# ProPrj_UNO_SIG_pro_2026-06-11.net
KiCad netlist of a schematic drawn in EasyEDA Pro
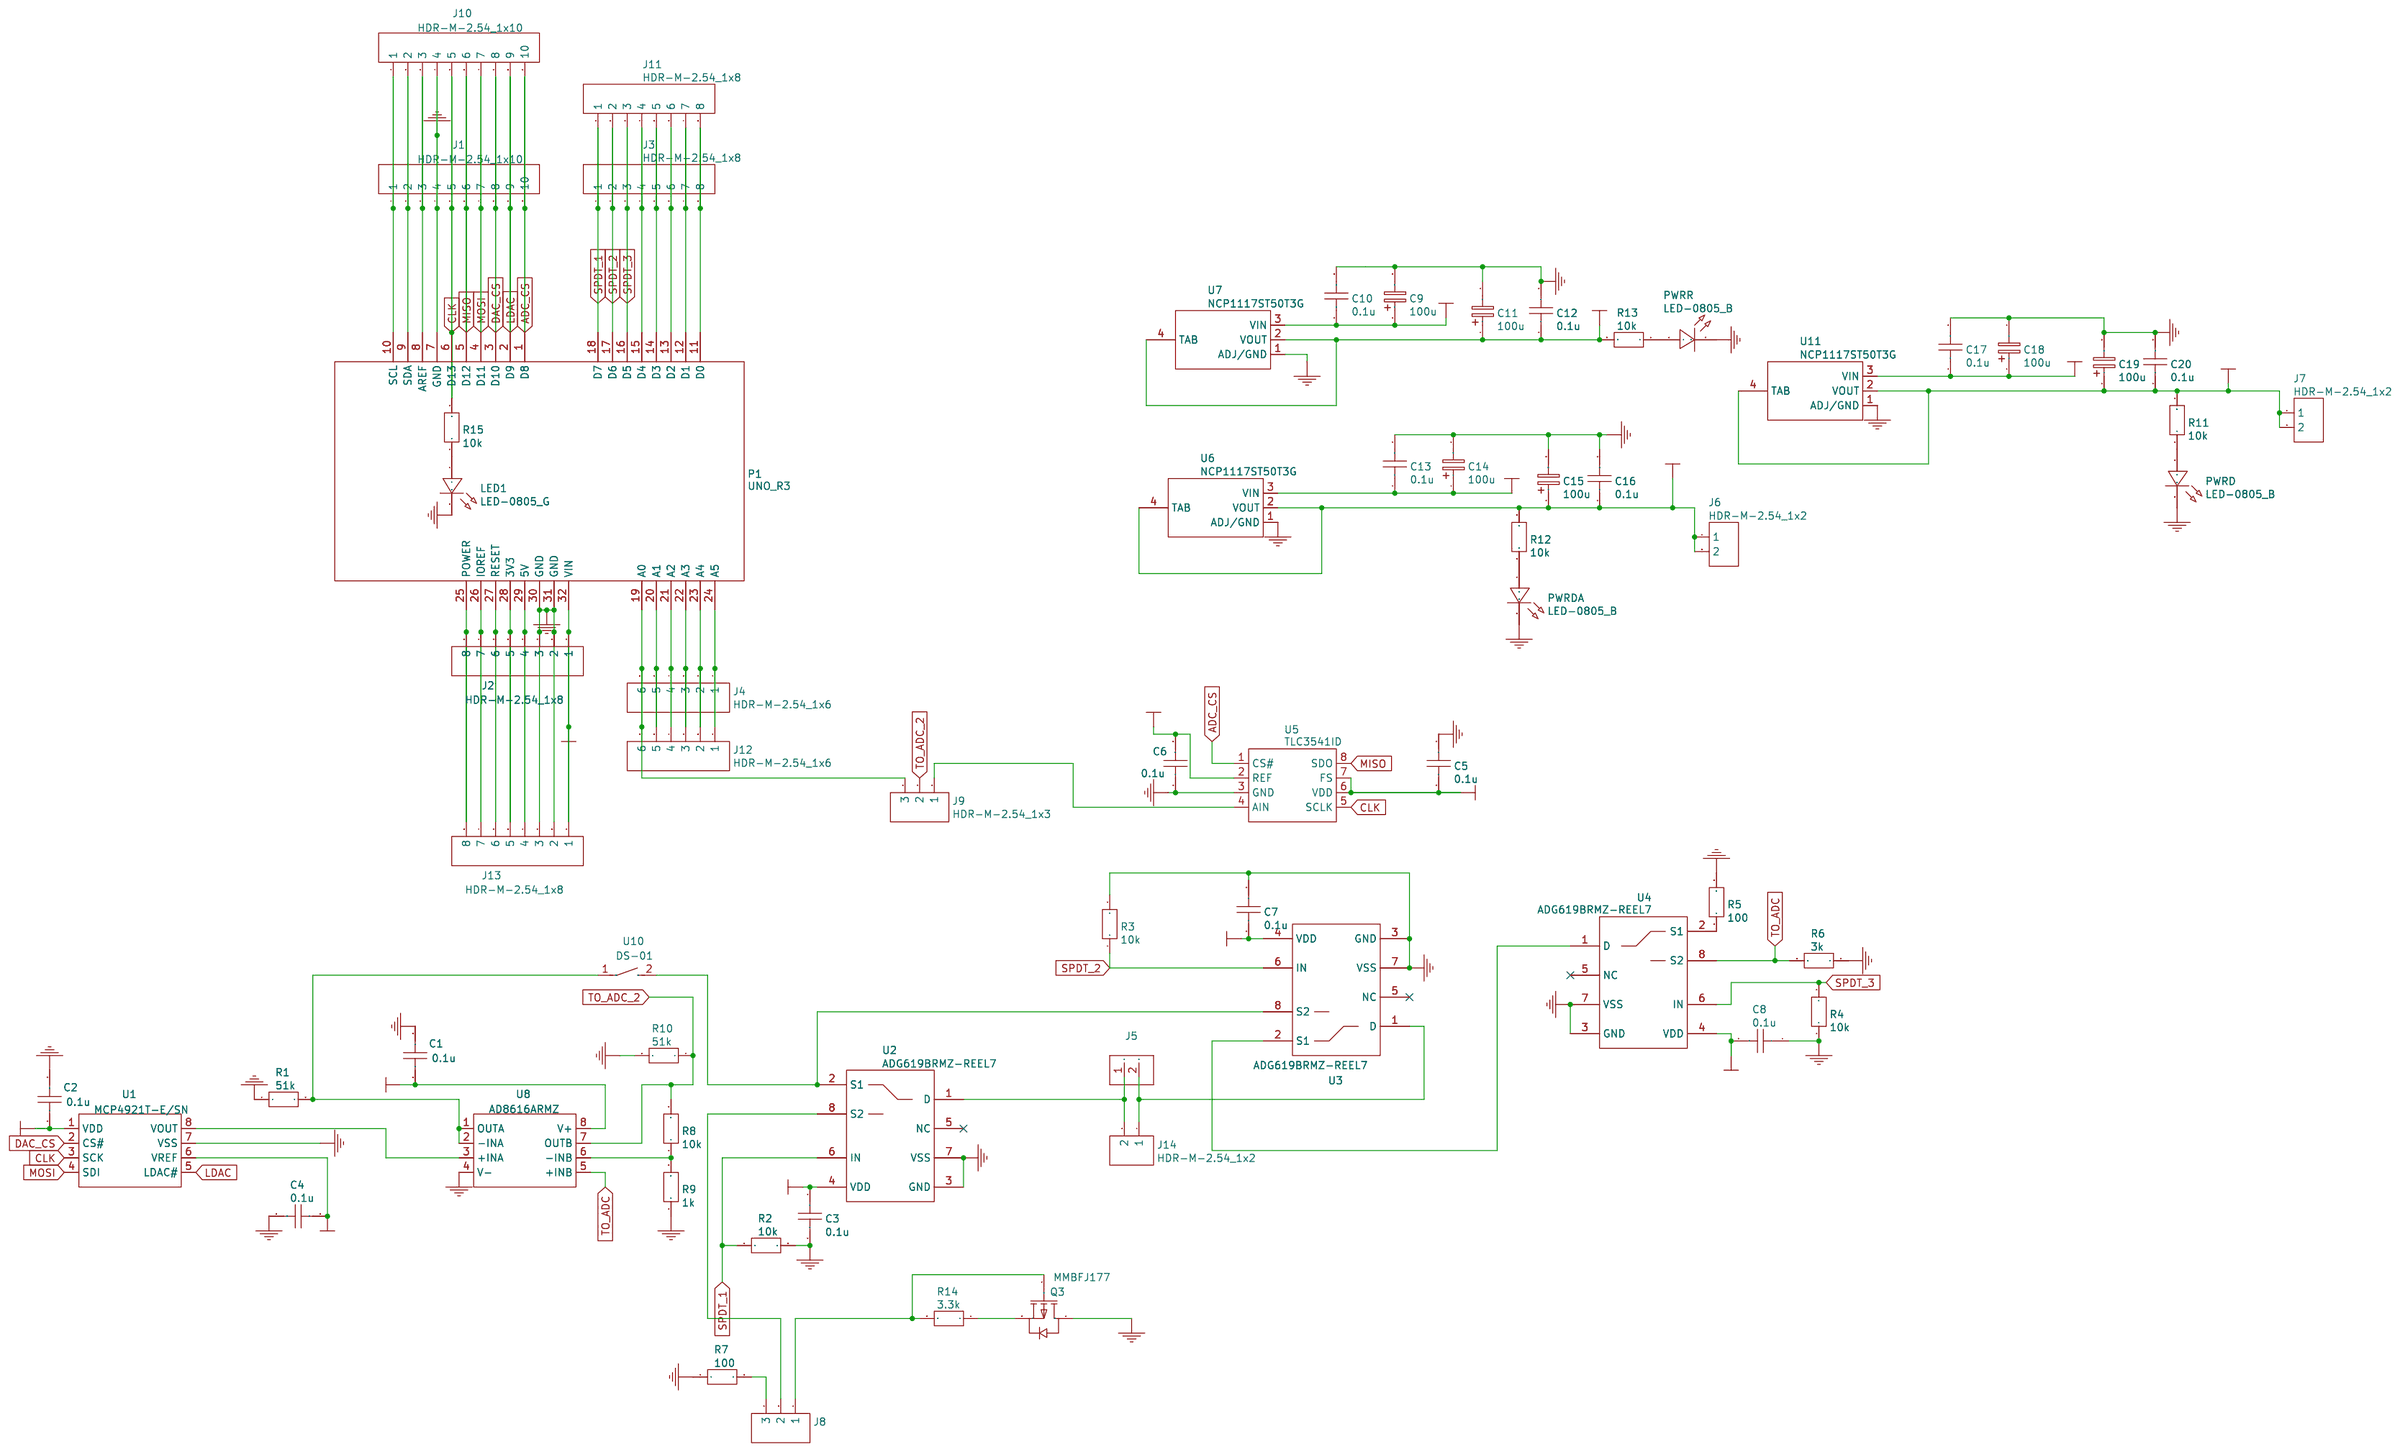
[diagram p0: schematic sheet]

(export (version "E")
  (design (tool "Eeschema 10.0.6"))
  (components
    (comp (ref "C1")
      (value "0.1u")
      (footprint "easyedapro:C0805")
      (libsource (lib "easyedapro") (part "0.1u"))
    )
    (comp (ref "C2")
      (value "0.1u")
      (footprint "easyedapro:C0805")
      (libsource (lib "easyedapro") (part "0.1u"))
    )
    (comp (ref "C3")
      (value "0.1u")
      (footprint "easyedapro:C0805")
      (libsource (lib "easyedapro") (part "0.1u"))
    )
    (comp (ref "C4")
      (value "0.1u")
      (footprint "easyedapro:C0805")
      (libsource (lib "easyedapro") (part "0.1u"))
    )
    (comp (ref "C5")
      (value "0.1u")
      (footprint "easyedapro:C0805")
      (libsource (lib "easyedapro") (part "0.1u"))
    )
    (comp (ref "C6")
      (value "0.1u")
      (footprint "easyedapro:C0805")
      (libsource (lib "easyedapro") (part "0.1u"))
    )
    (comp (ref "C7")
      (value "0.1u")
      (footprint "easyedapro:C0805")
      (libsource (lib "easyedapro") (part "0.1u"))
    )
    (comp (ref "C8")
      (value "0.1u")
      (footprint "easyedapro:C0805")
      (libsource (lib "easyedapro") (part "0.1u"))
    )
    (comp (ref "C9")
      (value "100u")
      (footprint "easyedapro:CAP-D8.0×F3.5")
      (libsource (lib "easyedapro") (part "100u"))
    )
    (comp (ref "C10")
      (value "0.1u")
      (footprint "easyedapro:C0805")
      (libsource (lib "easyedapro") (part "0.1u"))
    )
    (comp (ref "C11")
      (value "100u")
      (footprint "easyedapro:CAP-D8.0×F3.5")
      (libsource (lib "easyedapro") (part "100u"))
    )
    (comp (ref "C12")
      (value "0.1u")
      (footprint "easyedapro:C0805")
      (libsource (lib "easyedapro") (part "0.1u"))
    )
    (comp (ref "C13")
      (value "0.1u")
      (footprint "easyedapro:C0805")
      (libsource (lib "easyedapro") (part "0.1u"))
    )
    (comp (ref "C14")
      (value "100u")
      (footprint "easyedapro:CAP-D8.0×F3.5")
      (libsource (lib "easyedapro") (part "100u"))
    )
    (comp (ref "C15")
      (value "100u")
      (footprint "easyedapro:CAP-D8.0×F3.5")
      (libsource (lib "easyedapro") (part "100u"))
    )
    (comp (ref "C16")
      (value "0.1u")
      (footprint "easyedapro:C0805")
      (libsource (lib "easyedapro") (part "0.1u"))
    )
    (comp (ref "C17")
      (value "0.1u")
      (footprint "easyedapro:C0805")
      (libsource (lib "easyedapro") (part "0.1u"))
    )
    (comp (ref "C18")
      (value "100u")
      (footprint "easyedapro:CAP-D8.0×F3.5")
      (libsource (lib "easyedapro") (part "100u"))
    )
    (comp (ref "C19")
      (value "100u")
      (footprint "easyedapro:CAP-D8.0×F3.5")
      (libsource (lib "easyedapro") (part "100u"))
    )
    (comp (ref "C20")
      (value "0.1u")
      (footprint "easyedapro:C0805")
      (libsource (lib "easyedapro") (part "0.1u"))
    )
    (comp (ref "J1")
      (value "HDR-M-2.54_1x10")
      (footprint "easyedapro:HDR-M-2.54_1X10")
      (libsource (lib "easyedapro") (part "HDR-M-2.54_1x10"))
    )
    (comp (ref "J2")
      (value "HDR-M-2.54_1x8")
      (footprint "easyedapro:HDR-M-2.54_1X8")
      (libsource (lib "easyedapro") (part "HDR-M-2.54_1x8"))
    )
    (comp (ref "J3")
      (value "HDR-M-2.54_1x8")
      (footprint "easyedapro:HDR-M-2.54_1X8")
      (libsource (lib "easyedapro") (part "HDR-M-2.54_1x8"))
    )
    (comp (ref "J4")
      (value "HDR-M-2.54_1x6")
      (footprint "easyedapro:HDR-M-2.54_1X6")
      (libsource (lib "easyedapro") (part "HDR-M-2.54_1x6"))
    )
    (comp (ref "J5")
      (value "CON_TERMINAL_BLOCK_02-5MM")
      (footprint "easyedapro:TERMINAL_BLOCK_2P_5")
      (libsource (lib "easyedapro") (part "CON_TERMINAL_BLOCK_02-5MM"))
    )
    (comp (ref "J6")
      (value "HDR-M-2.54_1x2")
      (footprint "easyedapro:HDR-M-2.54_1X2")
      (libsource (lib "easyedapro") (part "HDR-M-2.54_1x2"))
    )
    (comp (ref "J7")
      (value "HDR-M-2.54_1x2")
      (footprint "easyedapro:HDR-M-2.54_1X2")
      (libsource (lib "easyedapro") (part "HDR-M-2.54_1x2"))
    )
    (comp (ref "J8")
      (value "HDR-M-2.54_1x3")
      (footprint "easyedapro:HDR-M-2.54_1X3")
      (libsource (lib "easyedapro") (part "HDR-M-2.54_1x3"))
    )
    (comp (ref "J9")
      (value "HDR-M-2.54_1x3")
      (footprint "easyedapro:HDR-M-2.54_1X3")
      (libsource (lib "easyedapro") (part "HDR-M-2.54_1x3"))
    )
    (comp (ref "J10")
      (value "HDR-M-2.54_1x10")
      (footprint "easyedapro:HDR-M-2.54_1X10")
      (libsource (lib "easyedapro") (part "HDR-M-2.54_1x10"))
    )
    (comp (ref "J11")
      (value "HDR-M-2.54_1x8")
      (footprint "easyedapro:HDR-M-2.54_1X8")
      (libsource (lib "easyedapro") (part "HDR-M-2.54_1x8"))
    )
    (comp (ref "J12")
      (value "HDR-M-2.54_1x6")
      (footprint "easyedapro:HDR-M-2.54_1X6")
      (libsource (lib "easyedapro") (part "HDR-M-2.54_1x6"))
    )
    (comp (ref "J13")
      (value "HDR-M-2.54_1x8")
      (footprint "easyedapro:HDR-M-2.54_1X8")
      (libsource (lib "easyedapro") (part "HDR-M-2.54_1x8"))
    )
    (comp (ref "J14")
      (value "HDR-M-2.54_1x2")
      (footprint "easyedapro:HDR-M-2.54_1X2")
      (libsource (lib "easyedapro") (part "HDR-M-2.54_1x2"))
    )
    (comp (ref "LED1")
      (value "LED-0805_G")
      (footprint "easyedapro:LED0805_GREEN")
      (fields (field (name "Manufacturer Part") "NCD0805G1") (field (name "Manufacturer") "国星光电"))
      (libsource (lib "easyedapro") (part "LED-0805_G"))
    )
    (comp (ref "P1") (value "UNO_R3") (libsource (lib "easyedapro") (part "UNO_R3")))
    (comp (ref "PWRD")
      (value "LED-0805_B")
      (footprint "easyedapro:LED0805_BLUE")
      (fields (field (name "Manufacturer Part") "D-B080508B1-KS2") (field (name "Manufacturer") "方舟 ARKLED"))
      (libsource (lib "easyedapro") (part "LED-0805_B"))
    )
    (comp (ref "PWRDA")
      (value "LED-0805_B")
      (footprint "easyedapro:LED0805_BLUE")
      (fields (field (name "Manufacturer Part") "D-B080508B1-KS2") (field (name "Manufacturer") "方舟 ARKLED"))
      (libsource (lib "easyedapro") (part "LED-0805_B"))
    )
    (comp (ref "PWRR")
      (value "LED-0805_B")
      (footprint "easyedapro:LED0805_BLUE")
      (fields (field (name "Manufacturer Part") "D-B080508B1-KS2") (field (name "Manufacturer") "方舟 ARKLED"))
      (libsource (lib "easyedapro") (part "LED-0805_B"))
    )
    (comp (ref "Q3")
      (value "MMBFJ177")
      (footprint "easyedapro:SOT-23-3_L3.0-W1.7-P0.95-LS2.9-BR")
      (fields (field (name "Manufacturer") "onsemi(安森美)"))
      (libsource (lib "easyedapro") (part "MMBFJ177"))
    )
    (comp (ref "R1") (value "51k") (footprint "easyedapro:R1206") (libsource (lib "easyedapro") (part "51k")))
    (comp (ref "R2") (value "10k") (footprint "easyedapro:R1206") (libsource (lib "easyedapro") (part "10k")))
    (comp (ref "R3") (value "10k") (footprint "easyedapro:R1206") (libsource (lib "easyedapro") (part "10k")))
    (comp (ref "R4") (value "10k") (footprint "easyedapro:R1206") (libsource (lib "easyedapro") (part "10k")))
    (comp (ref "R5") (value "100") (footprint "easyedapro:R1206") (libsource (lib "easyedapro") (part "100")))
    (comp (ref "R6") (value "3k") (footprint "easyedapro:R1206") (libsource (lib "easyedapro") (part "3k")))
    (comp (ref "R7") (value "100") (footprint "easyedapro:R1206") (libsource (lib "easyedapro") (part "100")))
    (comp (ref "R8") (value "10k") (footprint "easyedapro:R1206") (libsource (lib "easyedapro") (part "10k")))
    (comp (ref "R9") (value "1k") (footprint "easyedapro:R1206") (libsource (lib "easyedapro") (part "1k")))
    (comp (ref "R10")
      (value "51k")
      (footprint "easyedapro:R1206")
      (libsource (lib "easyedapro") (part "51k"))
    )
    (comp (ref "R11")
      (value "10k")
      (footprint "easyedapro:R1206")
      (libsource (lib "easyedapro") (part "10k"))
    )
    (comp (ref "R12")
      (value "10k")
      (footprint "easyedapro:R1206")
      (libsource (lib "easyedapro") (part "10k"))
    )
    (comp (ref "R13")
      (value "10k")
      (footprint "easyedapro:R1206")
      (libsource (lib "easyedapro") (part "10k"))
    )
    (comp (ref "R14")
      (value "3.3k")
      (footprint "easyedapro:R1206")
      (libsource (lib "easyedapro") (part "3.3k"))
    )
    (comp (ref "R15")
      (value "10k")
      (footprint "easyedapro:R1206")
      (libsource (lib "easyedapro") (part "10k"))
    )
    (comp (ref "U1")
      (value "MCP4921T-E/SN")
      (footprint "easyedapro:SOIC-8_L4.9-W3.9-P1.27-LS6.0-BL-2")
      (fields (field (name "Manufacturer") "MICROCHIP(美国微芯)"))
      (libsource (lib "easyedapro") (part "MCP4921T-E/SN"))
    )
    (comp (ref "U2")
      (value "ADG619BRMZ-REEL7")
      (footprint "easyedapro:MSOP-8_L3.0-W3.0-P0.65-LS4.9-TL")
      (fields (field (name "Manufacturer") "ADI(亚德诺)/LINEAR(凌特)"))
      (libsource (lib "easyedapro") (part "ADG619BRMZ-REEL7"))
    )
    (comp (ref "U3")
      (value "ADG619BRMZ-REEL7")
      (footprint "easyedapro:MSOP-8_L3.0-W3.0-P0.65-LS4.9-TL")
      (fields (field (name "Manufacturer") "ADI(亚德诺)/LINEAR(凌特)"))
      (libsource (lib "") (part "ADG619BRMZ-REEL7_1"))
    )
    (comp (ref "U4")
      (value "ADG619BRMZ-REEL7")
      (footprint "easyedapro:MSOP-8_L3.0-W3.0-P0.65-LS4.9-TL")
      (fields (field (name "Manufacturer") "ADI(亚德诺)/LINEAR(凌特)"))
      (libsource (lib "") (part "ADG619BRMZ-REEL7_2"))
    )
    (comp (ref "U5")
      (value "TLC3541ID")
      (footprint "easyedapro:SOIC-8_L4.9-W3.9-P1.27-LS6.0-BL")
      (fields (field (name "Manufacturer") "TI(德州仪器)"))
      (libsource (lib "easyedapro") (part "TLC3541ID"))
    )
    (comp (ref "U6")
      (value "NCP1117ST50T3G")
      (footprint "easyedapro:SOT-223_L6.5-W3.5-P2.30-LS7.0-BR")
      (fields (field (name "Manufacturer") "onsemi(安森美)"))
      (libsource (lib "easyedapro") (part "NCP1117ST50T3G"))
    )
    (comp (ref "U7")
      (value "NCP1117ST50T3G")
      (footprint "easyedapro:SOT-223_L6.5-W3.5-P2.30-LS7.0-BR")
      (fields (field (name "Manufacturer") "onsemi(安森美)"))
      (libsource (lib "easyedapro") (part "NCP1117ST50T3G"))
    )
    (comp (ref "U8")
      (value "AD8616ARMZ")
      (footprint "easyedapro:MSOP-8_L3.0-W3.0-P0.65-LS4.9-BL")
      (fields (field (name "Manufacturer") "ADI(亚德诺)/LINEAR(凌特)"))
      (libsource (lib "easyedapro") (part "AD8616ARMZ"))
    )
    (comp (ref "U10")
      (value "DS-01")
      (footprint "easyedapro:SW-TH_DS-01")
      (libsource (lib "easyedapro") (part "DS-01"))
    )
    (comp (ref "U11")
      (value "NCP1117ST50T3G")
      (footprint "easyedapro:SOT-223_L6.5-W3.5-P2.30-LS7.0-BR")
      (fields (field (name "Manufacturer") "onsemi(安森美)"))
      (libsource (lib "easyedapro") (part "NCP1117ST50T3G"))
    )
  )
  (nets
    (net (code "1") (name "+12V") (class "Default")
      (node (ref "C10") (pin "1") (pinfunction "1_1") (pintype "unspecified"))
      (node (ref "C13") (pin "1") (pinfunction "1_1") (pintype "unspecified"))
      (node (ref "C14") (pin "1") (pinfunction "1_1") (pintype "unspecified"))
      (node (ref "C17") (pin "1") (pinfunction "1_1") (pintype "unspecified"))
      (node (ref "C18") (pin "1") (pinfunction "1_1") (pintype "unspecified"))
      (node (ref "C9") (pin "1") (pinfunction "1_1") (pintype "unspecified"))
      (node (ref "J13") (pin "1") (pinfunction "1_1") (pintype "unspecified"))
      (node (ref "J2") (pin "1") (pinfunction "1_1") (pintype "unspecified"))
      (node (ref "P1") (pin "32") (pinfunction "VIN_32") (pintype "unspecified"))
      (node (ref "U11") (pin "3") (pinfunction "VIN_3") (pintype "unspecified"))
      (node (ref "U6") (pin "3") (pinfunction "VIN_3") (pintype "unspecified"))
      (node (ref "U7") (pin "3") (pinfunction "VIN_3") (pintype "unspecified"))
    )
    (net (code "2") (name "ADC_CS") (class "Default")
      (node (ref "J1") (pin "10") (pinfunction "10_10") (pintype "unspecified"))
      (node (ref "J10") (pin "10") (pinfunction "10_10") (pintype "unspecified"))
      (node (ref "P1") (pin "1") (pinfunction "D8_1") (pintype "unspecified"))
      (node (ref "U5") (pin "1") (pinfunction "CS#_1") (pintype "unspecified"))
    )
    (net (code "3") (name "CLK") (class "Default")
      (node (ref "J1") (pin "5") (pinfunction "5_5") (pintype "unspecified"))
      (node (ref "J10") (pin "5") (pinfunction "5_5") (pintype "unspecified"))
      (node (ref "P1") (pin "6") (pinfunction "D13_6") (pintype "unspecified"))
      (node (ref "R15") (pin "2") (pinfunction "2_2") (pintype "unspecified"))
      (node (ref "U1") (pin "3") (pinfunction "SCK_3") (pintype "unspecified"))
      (node (ref "U5") (pin "5") (pinfunction "SCLK_5") (pintype "unspecified"))
    )
    (net (code "4") (name "DAC_CS") (class "Default")
      (node (ref "J1") (pin "8") (pinfunction "8_8") (pintype "unspecified"))
      (node (ref "J10") (pin "8") (pinfunction "8_8") (pintype "unspecified"))
      (node (ref "P1") (pin "3") (pinfunction "D10_3") (pintype "unspecified"))
      (node (ref "U1") (pin "2") (pinfunction "CS#_2") (pintype "unspecified"))
    )
    (net (code "5") (name "GND") (class "Default")
      (node (ref "C1") (pin "2") (pinfunction "2_2") (pintype "unspecified"))
      (node (ref "C10") (pin "2") (pinfunction "2_2") (pintype "unspecified"))
      (node (ref "C11") (pin "2") (pinfunction "2_2") (pintype "unspecified"))
      (node (ref "C12") (pin "2") (pinfunction "2_2") (pintype "unspecified"))
      (node (ref "C13") (pin "2") (pinfunction "2_2") (pintype "unspecified"))
      (node (ref "C14") (pin "2") (pinfunction "2_2") (pintype "unspecified"))
      (node (ref "C15") (pin "2") (pinfunction "2_2") (pintype "unspecified"))
      (node (ref "C16") (pin "2") (pinfunction "2_2") (pintype "unspecified"))
      (node (ref "C17") (pin "2") (pinfunction "2_2") (pintype "unspecified"))
      (node (ref "C18") (pin "2") (pinfunction "2_2") (pintype "unspecified"))
      (node (ref "C19") (pin "2") (pinfunction "2_2") (pintype "unspecified"))
      (node (ref "C2") (pin "2") (pinfunction "2_2") (pintype "unspecified"))
      (node (ref "C20") (pin "2") (pinfunction "2_2") (pintype "unspecified"))
      (node (ref "C3") (pin "2") (pinfunction "2_2") (pintype "unspecified"))
      (node (ref "C4") (pin "2") (pinfunction "2_2") (pintype "unspecified"))
      (node (ref "C5") (pin "2") (pinfunction "2_2") (pintype "unspecified"))
      (node (ref "C6") (pin "1") (pinfunction "1_1") (pintype "unspecified"))
      (node (ref "C7") (pin "1") (pinfunction "1_1") (pintype "unspecified"))
      (node (ref "C8") (pin "1") (pinfunction "1_1") (pintype "unspecified"))
      (node (ref "C9") (pin "2") (pinfunction "2_2") (pintype "unspecified"))
      (node (ref "J1") (pin "4") (pinfunction "4_4") (pintype "unspecified"))
      (node (ref "J10") (pin "4") (pinfunction "4_4") (pintype "unspecified"))
      (node (ref "J13") (pin "2") (pinfunction "2_2") (pintype "unspecified"))
      (node (ref "J13") (pin "3") (pinfunction "3_3") (pintype "unspecified"))
      (node (ref "J2") (pin "2") (pinfunction "2_2") (pintype "unspecified"))
      (node (ref "J2") (pin "3") (pinfunction "3_3") (pintype "unspecified"))
      (node (ref "LED1") (pin "2") (pinfunction "2_2") (pintype "unspecified"))
      (node (ref "P1") (pin "30") (pinfunction "GND_30") (pintype "unspecified"))
      (node (ref "P1") (pin "31") (pinfunction "GND_31") (pintype "unspecified"))
      (node (ref "P1") (pin "7") (pinfunction "GND_7") (pintype "unspecified"))
      (node (ref "PWRD") (pin "2") (pinfunction "2_2") (pintype "unspecified"))
      (node (ref "PWRDA") (pin "2") (pinfunction "2_2") (pintype "unspecified"))
      (node (ref "PWRR") (pin "2") (pinfunction "2_2") (pintype "unspecified"))
      (node (ref "Q3") (pin "1") (pinfunction "D_1") (pintype "unspecified"))
      (node (ref "R1") (pin "1") (pinfunction "1_1") (pintype "unspecified"))
      (node (ref "R10") (pin "2") (pinfunction "2_2") (pintype "unspecified"))
      (node (ref "R2") (pin "2") (pinfunction "2_2") (pintype "unspecified"))
      (node (ref "R3") (pin "2") (pinfunction "2_2") (pintype "unspecified"))
      (node (ref "R4") (pin "1") (pinfunction "1_1") (pintype "unspecified"))
      (node (ref "R5") (pin "2") (pinfunction "2_2") (pintype "unspecified"))
      (node (ref "R6") (pin "1") (pinfunction "1_1") (pintype "unspecified"))
      (node (ref "R7") (pin "1") (pinfunction "1_1") (pintype "unspecified"))
      (node (ref "R9") (pin "1") (pinfunction "1_1") (pintype "unspecified"))
      (node (ref "U1") (pin "7") (pinfunction "VSS_7") (pintype "unspecified"))
      (node (ref "U11") (pin "1") (pinfunction "ADJ/GND_1") (pintype "unspecified"))
      (node (ref "U2") (pin "3") (pinfunction "GND_3") (pintype "unspecified"))
      (node (ref "U2") (pin "7") (pinfunction "VSS_7") (pintype "unspecified"))
      (node (ref "U3") (pin "3") (pinfunction "GND_3") (pintype "unspecified"))
      (node (ref "U3") (pin "7") (pinfunction "VSS_7") (pintype "unspecified"))
      (node (ref "U4") (pin "3") (pinfunction "GND_3") (pintype "unspecified"))
      (node (ref "U4") (pin "7") (pinfunction "VSS_7") (pintype "unspecified"))
      (node (ref "U5") (pin "3") (pinfunction "GND_3") (pintype "unspecified"))
      (node (ref "U6") (pin "1") (pinfunction "ADJ/GND_1") (pintype "unspecified"))
      (node (ref "U7") (pin "1") (pinfunction "ADJ/GND_1") (pintype "unspecified"))
      (node (ref "U8") (pin "4") (pinfunction "V-_4") (pintype "unspecified"))
    )
    (net (code "6") (name "LDAC") (class "Default")
      (node (ref "J1") (pin "9") (pinfunction "9_9") (pintype "unspecified"))
      (node (ref "J10") (pin "9") (pinfunction "9_9") (pintype "unspecified"))
      (node (ref "P1") (pin "2") (pinfunction "D9_2") (pintype "unspecified"))
      (node (ref "U1") (pin "5") (pinfunction "LDAC#_5") (pintype "unspecified"))
    )
    (net (code "7") (name "MISO") (class "Default")
      (node (ref "J1") (pin "6") (pinfunction "6_6") (pintype "unspecified"))
      (node (ref "J10") (pin "6") (pinfunction "6_6") (pintype "unspecified"))
      (node (ref "P1") (pin "5") (pinfunction "D12_5") (pintype "unspecified"))
      (node (ref "U5") (pin "8") (pinfunction "SDO_8") (pintype "unspecified"))
    )
    (net (code "8") (name "MOSI") (class "Default")
      (node (ref "J1") (pin "7") (pinfunction "7_7") (pintype "unspecified"))
      (node (ref "J10") (pin "7") (pinfunction "7_7") (pintype "unspecified"))
      (node (ref "P1") (pin "4") (pinfunction "D11_4") (pintype "unspecified"))
      (node (ref "U1") (pin "4") (pinfunction "SDI_4") (pintype "unspecified"))
    )
    (net (code "9") (name "Net-(J8-Pad3)") (class "Default")
      (node (ref "J8") (pin "3") (pinfunction "3_3") (pintype "input"))
      (node (ref "R7") (pin "2") (pinfunction "2_2") (pintype "unspecified"))
    )
    (net (code "10") (name "Net-(LED1-Pad1)") (class "Default")
      (node (ref "LED1") (pin "1") (pinfunction "1_1") (pintype "unspecified"))
      (node (ref "R15") (pin "1") (pinfunction "1_1") (pintype "unspecified"))
    )
    (net (code "11") (name "Net-(P1-3V3)") (class "Default")
      (node (ref "J13") (pin "5") (pinfunction "5_5") (pintype "unspecified"))
      (node (ref "J2") (pin "5") (pinfunction "5_5") (pintype "unspecified"))
      (node (ref "P1") (pin "28") (pinfunction "3V3_28") (pintype "unspecified"))
    )
    (net (code "12") (name "Net-(P1-5V)") (class "Default")
      (node (ref "J13") (pin "4") (pinfunction "4_4") (pintype "unspecified"))
      (node (ref "J2") (pin "4") (pinfunction "4_4") (pintype "unspecified"))
      (node (ref "P1") (pin "29") (pinfunction "5V_29") (pintype "unspecified"))
    )
    (net (code "13") (name "Net-(P1-A0)") (class "Default")
      (node (ref "J12") (pin "6") (pinfunction "6_6") (pintype "input"))
      (node (ref "J4") (pin "6") (pinfunction "6_6") (pintype "input"))
      (node (ref "J9") (pin "3") (pinfunction "3_3") (pintype "input"))
      (node (ref "P1") (pin "19") (pinfunction "A0_19") (pintype "unspecified"))
    )
    (net (code "14") (name "Net-(P1-A1)") (class "Default")
      (node (ref "J12") (pin "5") (pinfunction "5_5") (pintype "input"))
      (node (ref "J4") (pin "5") (pinfunction "5_5") (pintype "input"))
      (node (ref "P1") (pin "20") (pinfunction "A1_20") (pintype "unspecified"))
    )
    (net (code "15") (name "Net-(P1-A2)") (class "Default")
      (node (ref "J12") (pin "4") (pinfunction "4_4") (pintype "input"))
      (node (ref "J4") (pin "4") (pinfunction "4_4") (pintype "input"))
      (node (ref "P1") (pin "21") (pinfunction "A2_21") (pintype "unspecified"))
    )
    (net (code "16") (name "Net-(P1-A3)") (class "Default")
      (node (ref "J12") (pin "3") (pinfunction "3_3") (pintype "input"))
      (node (ref "J4") (pin "3") (pinfunction "3_3") (pintype "input"))
      (node (ref "P1") (pin "22") (pinfunction "A3_22") (pintype "unspecified"))
    )
    (net (code "17") (name "Net-(P1-A4)") (class "Default")
      (node (ref "J12") (pin "2") (pinfunction "2_2") (pintype "input"))
      (node (ref "J4") (pin "2") (pinfunction "2_2") (pintype "input"))
      (node (ref "P1") (pin "23") (pinfunction "A4_23") (pintype "unspecified"))
    )
    (net (code "18") (name "Net-(P1-A5)") (class "Default")
      (node (ref "J12") (pin "1") (pinfunction "1_1") (pintype "input"))
      (node (ref "J4") (pin "1") (pinfunction "1_1") (pintype "input"))
      (node (ref "P1") (pin "24") (pinfunction "A5_24") (pintype "unspecified"))
    )
    (net (code "19") (name "Net-(P1-AREF)") (class "Default")
      (node (ref "J1") (pin "3") (pinfunction "3_3") (pintype "unspecified"))
      (node (ref "J10") (pin "3") (pinfunction "3_3") (pintype "unspecified"))
      (node (ref "P1") (pin "8") (pinfunction "AREF_8") (pintype "unspecified"))
    )
    (net (code "20") (name "Net-(P1-D0)") (class "Default")
      (node (ref "J11") (pin "8") (pinfunction "8_8") (pintype "unspecified"))
      (node (ref "J3") (pin "8") (pinfunction "8_8") (pintype "unspecified"))
      (node (ref "P1") (pin "11") (pinfunction "D0_11") (pintype "unspecified"))
    )
    (net (code "21") (name "Net-(P1-D1)") (class "Default")
      (node (ref "J11") (pin "7") (pinfunction "7_7") (pintype "unspecified"))
      (node (ref "J3") (pin "7") (pinfunction "7_7") (pintype "unspecified"))
      (node (ref "P1") (pin "12") (pinfunction "D1_12") (pintype "unspecified"))
    )
    (net (code "22") (name "Net-(P1-D2)") (class "Default")
      (node (ref "J11") (pin "6") (pinfunction "6_6") (pintype "unspecified"))
      (node (ref "J3") (pin "6") (pinfunction "6_6") (pintype "unspecified"))
      (node (ref "P1") (pin "13") (pinfunction "D2_13") (pintype "unspecified"))
    )
    (net (code "23") (name "Net-(P1-D3)") (class "Default")
      (node (ref "J11") (pin "5") (pinfunction "5_5") (pintype "unspecified"))
      (node (ref "J3") (pin "5") (pinfunction "5_5") (pintype "unspecified"))
      (node (ref "P1") (pin "14") (pinfunction "D3_14") (pintype "unspecified"))
    )
    (net (code "24") (name "Net-(P1-D4)") (class "Default")
      (node (ref "J11") (pin "4") (pinfunction "4_4") (pintype "unspecified"))
      (node (ref "J3") (pin "4") (pinfunction "4_4") (pintype "unspecified"))
      (node (ref "P1") (pin "15") (pinfunction "D4_15") (pintype "unspecified"))
    )
    (net (code "25") (name "Net-(P1-IOREF)") (class "Default")
      (node (ref "J13") (pin "7") (pinfunction "7_7") (pintype "unspecified"))
      (node (ref "J2") (pin "7") (pinfunction "7_7") (pintype "unspecified"))
      (node (ref "P1") (pin "26") (pinfunction "IOREF_26") (pintype "unspecified"))
    )
    (net (code "26") (name "Net-(P1-POWER)") (class "Default")
      (node (ref "J13") (pin "8") (pinfunction "8_8") (pintype "unspecified"))
      (node (ref "J2") (pin "8") (pinfunction "8_8") (pintype "unspecified"))
      (node (ref "P1") (pin "25") (pinfunction "POWER_25") (pintype "unspecified"))
    )
    (net (code "27") (name "Net-(P1-RESET)") (class "Default")
      (node (ref "J13") (pin "6") (pinfunction "6_6") (pintype "unspecified"))
      (node (ref "J2") (pin "6") (pinfunction "6_6") (pintype "unspecified"))
      (node (ref "P1") (pin "27") (pinfunction "RESET_27") (pintype "unspecified"))
    )
    (net (code "28") (name "Net-(P1-SCL)") (class "Default")
      (node (ref "J1") (pin "1") (pinfunction "1_1") (pintype "unspecified"))
      (node (ref "J10") (pin "1") (pinfunction "1_1") (pintype "unspecified"))
      (node (ref "P1") (pin "10") (pinfunction "SCL_10") (pintype "unspecified"))
    )
    (net (code "29") (name "Net-(P1-SDA)") (class "Default")
      (node (ref "J1") (pin "2") (pinfunction "2_2") (pintype "unspecified"))
      (node (ref "J10") (pin "2") (pinfunction "2_2") (pintype "unspecified"))
      (node (ref "P1") (pin "9") (pinfunction "SDA_9") (pintype "unspecified"))
    )
    (net (code "30") (name "Net-(PWRD-Pad1)") (class "Default")
      (node (ref "PWRD") (pin "1") (pinfunction "1_1") (pintype "unspecified"))
      (node (ref "R11") (pin "1") (pinfunction "1_1") (pintype "unspecified"))
    )
    (net (code "31") (name "Net-(PWRDA-Pad1)") (class "Default")
      (node (ref "PWRDA") (pin "1") (pinfunction "1_1") (pintype "unspecified"))
      (node (ref "R12") (pin "1") (pinfunction "1_1") (pintype "unspecified"))
    )
    (net (code "32") (name "Net-(PWRR-Pad1)") (class "Default")
      (node (ref "PWRR") (pin "1") (pinfunction "1_1") (pintype "unspecified"))
      (node (ref "R13") (pin "1") (pinfunction "1_1") (pintype "unspecified"))
    )
    (net (code "33") (name "Net-(Q3-G)") (class "Default")
      (node (ref "J8") (pin "1") (pinfunction "1_1") (pintype "input"))
      (node (ref "Q3") (pin "3") (pinfunction "G_3") (pintype "unspecified"))
      (node (ref "R14") (pin "2") (pinfunction "2_2") (pintype "unspecified"))
    )
    (net (code "34") (name "Net-(Q3-S)") (class "Default")
      (node (ref "Q3") (pin "2") (pinfunction "S_2") (pintype "unspecified"))
      (node (ref "R14") (pin "1") (pinfunction "1_1") (pintype "unspecified"))
    )
    (net (code "35") (name "Net-(U1-VOUT)") (class "Default")
      (node (ref "U1") (pin "8") (pinfunction "VOUT_8") (pintype "unspecified"))
      (node (ref "U8") (pin "3") (pinfunction "+INA_3") (pintype "unspecified"))
    )
    (net (code "36") (name "Net-(U2-D)") (class "Default")
      (node (ref "J14") (pin "2") (pinfunction "2_2") (pintype "unspecified"))
      (node (ref "J5") (pin "1") (pinfunction "1_1") (pintype "unspecified"))
      (node (ref "U2") (pin "1") (pinfunction "D_1") (pintype "unspecified"))
    )
    (net (code "37") (name "Net-(U2-S1)") (class "Default")
      (node (ref "U10") (pin "2") (pinfunction "2_2") (pintype "unspecified"))
      (node (ref "U2") (pin "2") (pinfunction "S1_2") (pintype "unspecified"))
      (node (ref "U3") (pin "8") (pinfunction "S2_8") (pintype "unspecified"))
    )
    (net (code "38") (name "Net-(U2-S2)") (class "Default")
      (node (ref "J8") (pin "2") (pinfunction "2_2") (pintype "input"))
      (node (ref "U2") (pin "8") (pinfunction "S2_8") (pintype "unspecified"))
    )
    (net (code "39") (name "Net-(U3-D)") (class "Default")
      (node (ref "J14") (pin "1") (pinfunction "1_1") (pintype "unspecified"))
      (node (ref "J5") (pin "2") (pinfunction "2_2") (pintype "unspecified"))
      (node (ref "U3") (pin "1") (pinfunction "D_1") (pintype "unspecified"))
    )
    (net (code "40") (name "Net-(U3-S1)") (class "Default")
      (node (ref "U3") (pin "2") (pinfunction "S1_2") (pintype "unspecified"))
      (node (ref "U4") (pin "1") (pinfunction "D_1") (pintype "unspecified"))
    )
    (net (code "41") (name "Net-(U4-S1)") (class "Default")
      (node (ref "R5") (pin "1") (pinfunction "1_1") (pintype "unspecified"))
      (node (ref "U4") (pin "2") (pinfunction "S1_2") (pintype "unspecified"))
    )
    (net (code "42") (name "Net-(U5-AIN)") (class "Default")
      (node (ref "J9") (pin "1") (pinfunction "1_1") (pintype "input"))
      (node (ref "U5") (pin "4") (pinfunction "AIN_4") (pintype "unspecified"))
    )
    (net (code "43") (name "Net-(U8--INA)") (class "Default")
      (node (ref "R1") (pin "2") (pinfunction "2_2") (pintype "unspecified"))
      (node (ref "U10") (pin "1") (pinfunction "1_1") (pintype "unspecified"))
      (node (ref "U8") (pin "1") (pinfunction "OUTA_1") (pintype "unspecified"))
      (node (ref "U8") (pin "2") (pinfunction "-INA_2") (pintype "unspecified"))
    )
    (net (code "44") (name "Net-(U8--INB)") (class "Default")
      (node (ref "R8") (pin "1") (pinfunction "1_1") (pintype "unspecified"))
      (node (ref "R9") (pin "2") (pinfunction "2_2") (pintype "unspecified"))
      (node (ref "U8") (pin "6") (pinfunction "-INB_6") (pintype "unspecified"))
    )
    (net (code "45") (name "SPDT_1") (class "Default")
      (node (ref "J11") (pin "1") (pinfunction "1_1") (pintype "unspecified"))
      (node (ref "J3") (pin "1") (pinfunction "1_1") (pintype "unspecified"))
      (node (ref "P1") (pin "18") (pinfunction "D7_18") (pintype "unspecified"))
      (node (ref "R2") (pin "1") (pinfunction "1_1") (pintype "unspecified"))
      (node (ref "U2") (pin "6") (pinfunction "IN_6") (pintype "unspecified"))
    )
    (net (code "46") (name "SPDT_2") (class "Default")
      (node (ref "J11") (pin "2") (pinfunction "2_2") (pintype "unspecified"))
      (node (ref "J3") (pin "2") (pinfunction "2_2") (pintype "unspecified"))
      (node (ref "P1") (pin "17") (pinfunction "D6_17") (pintype "unspecified"))
      (node (ref "R3") (pin "1") (pinfunction "1_1") (pintype "unspecified"))
      (node (ref "U3") (pin "6") (pinfunction "IN_6") (pintype "unspecified"))
    )
    (net (code "47") (name "SPDT_3") (class "Default")
      (node (ref "J11") (pin "3") (pinfunction "3_3") (pintype "unspecified"))
      (node (ref "J3") (pin "3") (pinfunction "3_3") (pintype "unspecified"))
      (node (ref "P1") (pin "16") (pinfunction "D5_16") (pintype "unspecified"))
      (node (ref "R4") (pin "2") (pinfunction "2_2") (pintype "unspecified"))
      (node (ref "U4") (pin "6") (pinfunction "IN_6") (pintype "unspecified"))
    )
    (net (code "48") (name "TO_ADC") (class "Default")
      (node (ref "R6") (pin "2") (pinfunction "2_2") (pintype "unspecified"))
      (node (ref "U4") (pin "8") (pinfunction "S2_8") (pintype "unspecified"))
      (node (ref "U8") (pin "5") (pinfunction "+INB_5") (pintype "unspecified"))
    )
    (net (code "49") (name "TO_ADC_2") (class "Default")
      (node (ref "J9") (pin "2") (pinfunction "2_2") (pintype "input"))
      (node (ref "R10") (pin "1") (pinfunction "1_1") (pintype "unspecified"))
      (node (ref "R8") (pin "2") (pinfunction "2_2") (pintype "unspecified"))
      (node (ref "U8") (pin "7") (pinfunction "OUTB_7") (pintype "unspecified"))
    )
    (net (code "50") (name "VCCA") (class "Default")
      (node (ref "C1") (pin "1") (pinfunction "1_1") (pintype "unspecified"))
      (node (ref "C15") (pin "1") (pinfunction "1_1") (pintype "unspecified"))
      (node (ref "C16") (pin "1") (pinfunction "1_1") (pintype "unspecified"))
      (node (ref "C3") (pin "1") (pinfunction "1_1") (pintype "unspecified"))
      (node (ref "C7") (pin "2") (pinfunction "2_2") (pintype "unspecified"))
      (node (ref "C8") (pin "2") (pinfunction "2_2") (pintype "unspecified"))
      (node (ref "J6") (pin "1") (pinfunction "1_1") (pintype "unspecified"))
      (node (ref "J6") (pin "2") (pinfunction "2_2") (pintype "unspecified"))
      (node (ref "R12") (pin "2") (pinfunction "2_2") (pintype "unspecified"))
      (node (ref "U2") (pin "4") (pinfunction "VDD_4") (pintype "unspecified"))
      (node (ref "U3") (pin "4") (pinfunction "VDD_4") (pintype "unspecified"))
      (node (ref "U4") (pin "4") (pinfunction "VDD_4") (pintype "unspecified"))
      (node (ref "U6") (pin "2") (pinfunction "VOUT_2") (pintype "unspecified"))
      (node (ref "U6") (pin "4") (pinfunction "TAB_4") (pintype "unspecified"))
      (node (ref "U8") (pin "8") (pinfunction "V+_8") (pintype "unspecified"))
    )
    (net (code "51") (name "VCCD") (class "Default")
      (node (ref "C19") (pin "1") (pinfunction "1_1") (pintype "unspecified"))
      (node (ref "C2") (pin "1") (pinfunction "1_1") (pintype "unspecified"))
      (node (ref "C20") (pin "1") (pinfunction "1_1") (pintype "unspecified"))
      (node (ref "C5") (pin "1") (pinfunction "1_1") (pintype "unspecified"))
      (node (ref "J7") (pin "1") (pinfunction "1_1") (pintype "unspecified"))
      (node (ref "J7") (pin "2") (pinfunction "2_2") (pintype "unspecified"))
      (node (ref "R11") (pin "2") (pinfunction "2_2") (pintype "unspecified"))
      (node (ref "U1") (pin "1") (pinfunction "VDD_1") (pintype "unspecified"))
      (node (ref "U11") (pin "2") (pinfunction "VOUT_2") (pintype "unspecified"))
      (node (ref "U11") (pin "4") (pinfunction "TAB_4") (pintype "unspecified"))
      (node (ref "U5") (pin "6") (pinfunction "VDD_6") (pintype "unspecified"))
      (node (ref "U5") (pin "7") (pinfunction "FS_7") (pintype "unspecified"))
    )
    (net (code "52") (name "VCCREF") (class "Default")
      (node (ref "C11") (pin "1") (pinfunction "1_1") (pintype "unspecified"))
      (node (ref "C12") (pin "1") (pinfunction "1_1") (pintype "unspecified"))
      (node (ref "C4") (pin "1") (pinfunction "1_1") (pintype "unspecified"))
      (node (ref "C6") (pin "2") (pinfunction "2_2") (pintype "unspecified"))
      (node (ref "R13") (pin "2") (pinfunction "2_2") (pintype "unspecified"))
      (node (ref "U1") (pin "6") (pinfunction "VREF_6") (pintype "unspecified"))
      (node (ref "U5") (pin "2") (pinfunction "REF_2") (pintype "unspecified"))
      (node (ref "U7") (pin "2") (pinfunction "VOUT_2") (pintype "unspecified"))
      (node (ref "U7") (pin "4") (pinfunction "TAB_4") (pintype "unspecified"))
    )
    (net (code "53") (name "unconnected-(U2-NC-Pad5)") (class "Default")
      (node (ref "U2") (pin "5") (pinfunction "NC_5") (pintype "unspecified+no_connect"))
    )
    (net (code "54") (name "unconnected-(U3-NC-Pad5)") (class "Default")
      (node (ref "U3") (pin "5") (pinfunction "NC_5") (pintype "unspecified+no_connect"))
    )
    (net (code "55") (name "unconnected-(U4-NC-Pad5)") (class "Default")
      (node (ref "U4") (pin "5") (pinfunction "NC_5") (pintype "unspecified+no_connect"))
    )
  )
)
